# md_ver10_2.net
KiCad netlist of a schematic drawn in EAGLE
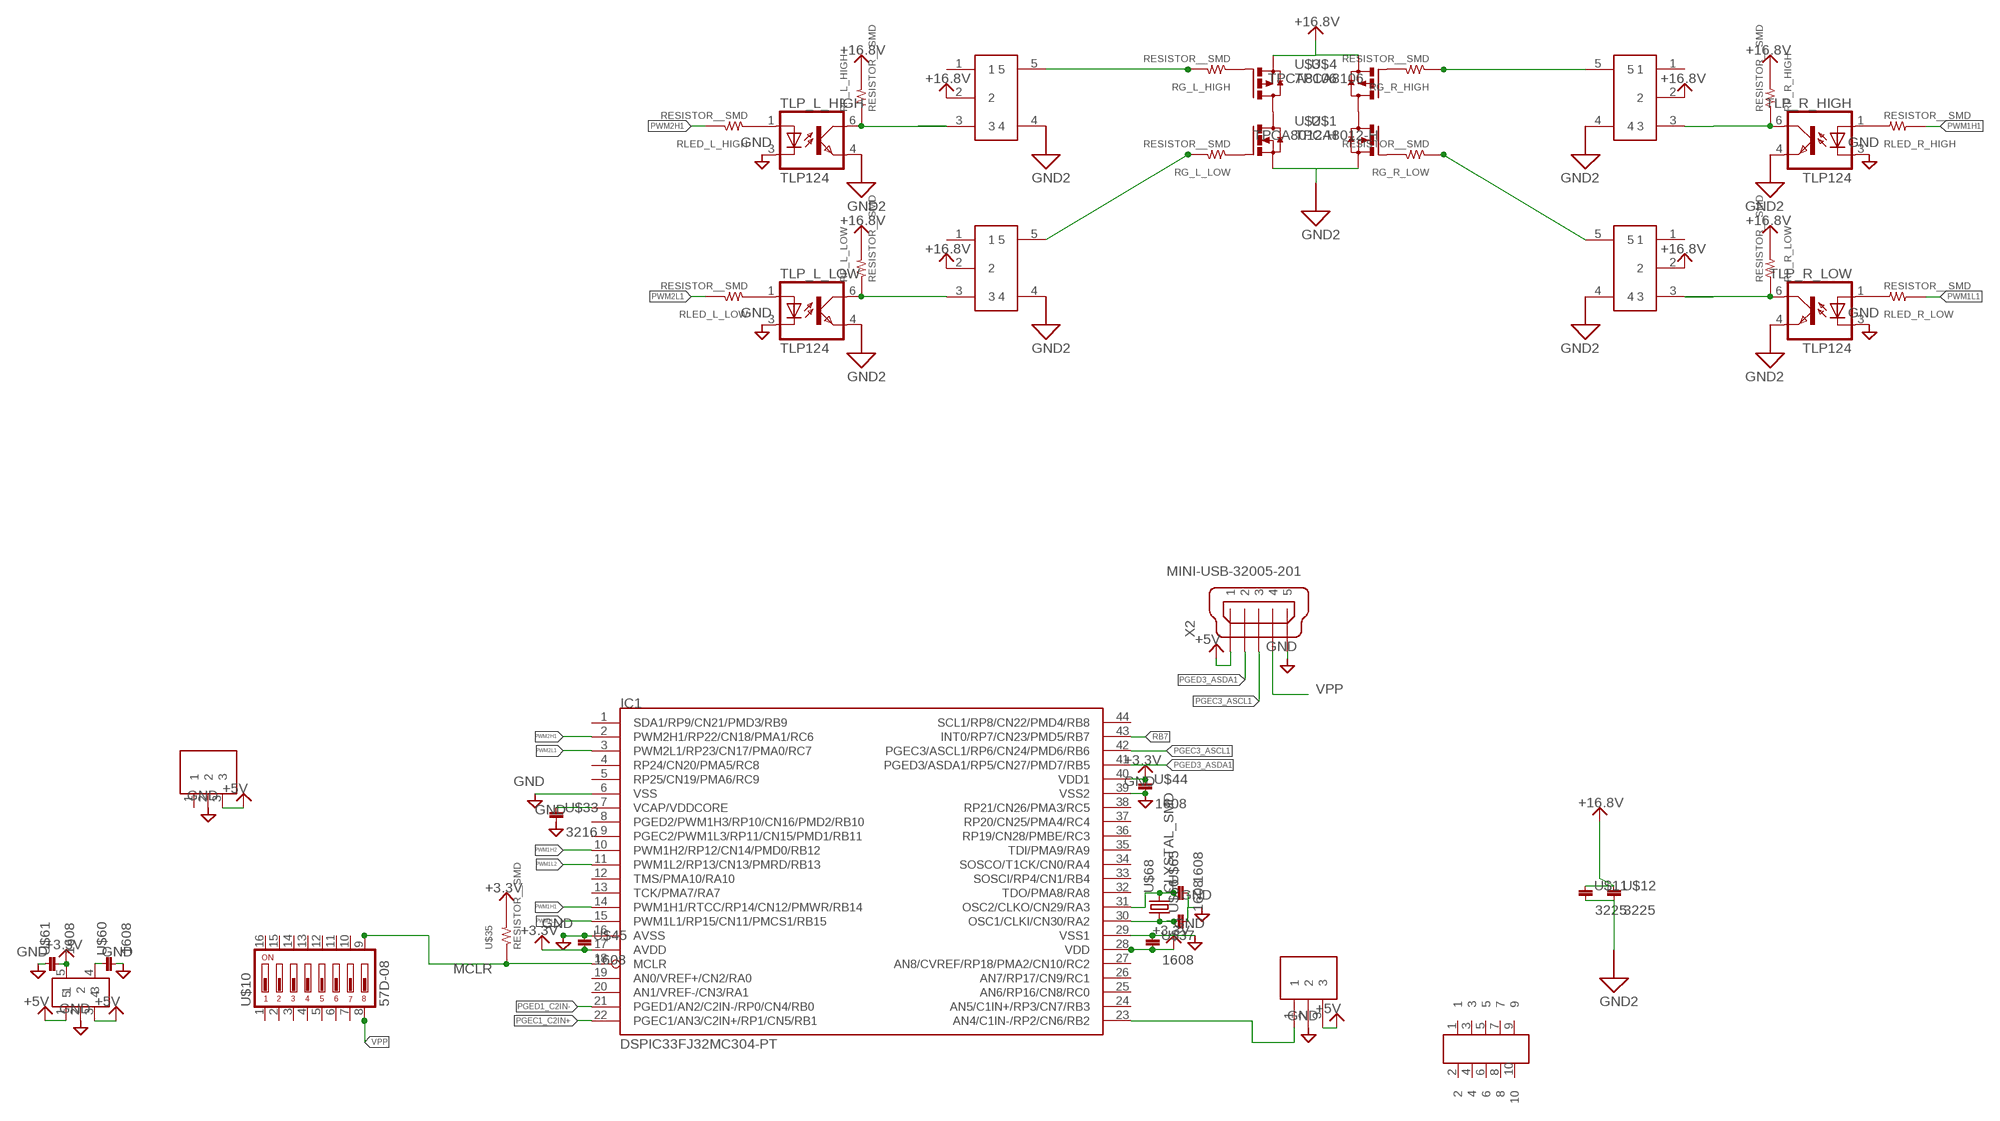
[diagram p0: schematic, sheet 1]

(export (version "E")
  (design (tool "Eeschema 10.0.6"))
  (components
    (comp (ref "IC1")
      (value "DSPIC33FJ32MC304-PT")
      (footprint "eagle-import:TQFP44")
      (libsource (lib "eagle-import") (part "DSPIC33FJ32MC304-PT"))
    )
    (comp (ref "IC_L_HIGH")
      (value "MCP1415")
      (footprint "eagle-import:SOT23-5L")
      (libsource (lib "eagle-import") (part "MCP1415"))
    )
    (comp (ref "IC_L_LOW")
      (value "MCP1415")
      (footprint "eagle-import:SOT23-5L")
      (libsource (lib "eagle-import") (part "MCP1415"))
    )
    (comp (ref "IC_R_HIGH")
      (value "MCP1415")
      (footprint "eagle-import:SOT23-5L")
      (libsource (lib "eagle-import") (part "MCP1415"))
    )
    (comp (ref "IC_R_LOW")
      (value "MCP1415")
      (footprint "eagle-import:SOT23-5L")
      (libsource (lib "eagle-import") (part "MCP1415"))
    )
    (comp (ref "RG_L_HIGH")
      (value "RESISTOR__SMD")
      (footprint "eagle-import:1608")
      (libsource (lib "eagle-import") (part "RESISTOR__SMD"))
    )
    (comp (ref "RG_L_LOW")
      (value "RESISTOR__SMD")
      (footprint "eagle-import:1608")
      (libsource (lib "eagle-import") (part "RESISTOR__SMD"))
    )
    (comp (ref "RG_R_HIGH")
      (value "RESISTOR__SMD")
      (footprint "eagle-import:1608")
      (libsource (lib "eagle-import") (part "RESISTOR__SMD"))
    )
    (comp (ref "RG_R_LOW")
      (value "RESISTOR__SMD")
      (footprint "eagle-import:1608")
      (libsource (lib "eagle-import") (part "RESISTOR__SMD"))
    )
    (comp (ref "RLED_L_HIGH")
      (value "RESISTOR__SMD")
      (footprint "eagle-import:1608")
      (libsource (lib "eagle-import") (part "RESISTOR__SMD"))
    )
    (comp (ref "RLED_L_LOW")
      (value "RESISTOR__SMD")
      (footprint "eagle-import:1608")
      (libsource (lib "eagle-import") (part "RESISTOR__SMD"))
    )
    (comp (ref "RLED_R_HIGH")
      (value "RESISTOR__SMD")
      (footprint "eagle-import:1608")
      (libsource (lib "eagle-import") (part "RESISTOR__SMD"))
    )
    (comp (ref "RLED_R_LOW")
      (value "RESISTOR__SMD")
      (footprint "eagle-import:1608")
      (libsource (lib "eagle-import") (part "RESISTOR__SMD"))
    )
    (comp (ref "RP_L_HIGH")
      (value "RESISTOR__SMD")
      (footprint "eagle-import:1608")
      (libsource (lib "eagle-import") (part "RESISTOR__SMD"))
    )
    (comp (ref "RP_L_LOW")
      (value "RESISTOR__SMD")
      (footprint "eagle-import:1608")
      (libsource (lib "eagle-import") (part "RESISTOR__SMD"))
    )
    (comp (ref "RP_R_HIGH")
      (value "RESISTOR__SMD")
      (footprint "eagle-import:1608")
      (libsource (lib "eagle-import") (part "RESISTOR__SMD"))
    )
    (comp (ref "RP_R_LOW")
      (value "RESISTOR__SMD")
      (footprint "eagle-import:1608")
      (libsource (lib "eagle-import") (part "RESISTOR__SMD"))
    )
    (comp (ref "TLP_L_HIGH")
      (value "TLP124")
      (footprint "eagle-import:11−4C1")
      (libsource (lib "eagle-import") (part "TLP124"))
    )
    (comp (ref "TLP_L_LOW")
      (value "TLP124")
      (footprint "eagle-import:11−4C1")
      (libsource (lib "eagle-import") (part "TLP124"))
    )
    (comp (ref "TLP_R_HIGH")
      (value "TLP124")
      (footprint "eagle-import:11−4C1")
      (libsource (lib "eagle-import") (part "TLP124"))
    )
    (comp (ref "TLP_R_LOW")
      (value "TLP124")
      (footprint "eagle-import:11−4C1")
      (libsource (lib "eagle-import") (part "TLP124"))
    )
    (comp (ref "U$1")
      (value "TPCA8012-H")
      (footprint "eagle-import:2-5Q1A")
      (libsource (lib "eagle-import") (part "TPCA8012-H"))
    )
    (comp (ref "U$2")
      (value "TPCA8012-H")
      (footprint "eagle-import:2-5Q1A")
      (libsource (lib "eagle-import") (part "TPCA8012-H"))
    )
    (comp (ref "U$3")
      (value "TPCA8106")
      (footprint "eagle-import:2-5Q1A")
      (libsource (lib "eagle-import") (part "TPCA8106"))
    )
    (comp (ref "U$4")
      (value "TPCA8106")
      (footprint "eagle-import:2-5Q1A")
      (libsource (lib "eagle-import") (part "TPCA8106"))
    )
    (comp (ref "U$7")
      (value "ＰＬ－ＩＲＭ")
      (footprint "eagle-import:ＰＬ－ＩＲＭ")
      (libsource (lib "eagle-import") (part "ＰＬ－ＩＲＭ"))
    )
    (comp (ref "U$8")
      (value "Ｒ－７８Ｅ５．０")
      (footprint "eagle-import:Ｒ－７８Ｅ５．０")
      (libsource (lib "eagle-import") (part "Ｒ－７８Ｅ５．０"))
    )
    (comp (ref "U$9")
      (value "TAR5SB")
      (footprint "eagle-import:SSOP5-P-0.95")
      (libsource (lib "eagle-import") (part "TAR5SB"))
    )
    (comp (ref "U$10")
      (value "57D-08")
      (footprint "eagle-import:57D")
      (libsource (lib "eagle-import") (part "57D-08"))
    )
    (comp (ref "U$11")
      (value "3225")
      (footprint "eagle-import:3225")
      (libsource (lib "eagle-import") (part "3225"))
    )
    (comp (ref "U$12")
      (value "3225")
      (footprint "eagle-import:3225")
      (libsource (lib "eagle-import") (part "3225"))
    )
    (comp (ref "U$15")
      (value "PIN_HEADER_52")
      (footprint "eagle-import:PIN_HEADER_5_2")
      (libsource (lib "eagle-import") (part "PIN_HEADER_52"))
    )
    (comp (ref "U$33")
      (value "3216")
      (footprint "eagle-import:3216")
      (libsource (lib "eagle-import") (part "3216"))
    )
    (comp (ref "U$35")
      (value "RESISTOR__SMD")
      (footprint "eagle-import:1608")
      (libsource (lib "eagle-import") (part "RESISTOR__SMD"))
    )
    (comp (ref "U$37")
      (value "1608")
      (footprint "eagle-import:1608")
      (libsource (lib "eagle-import") (part "1608"))
    )
    (comp (ref "U$44")
      (value "1608")
      (footprint "eagle-import:1608")
      (libsource (lib "eagle-import") (part "1608"))
    )
    (comp (ref "U$45")
      (value "1608")
      (footprint "eagle-import:1608")
      (libsource (lib "eagle-import") (part "1608"))
    )
    (comp (ref "U$60")
      (value "1608")
      (footprint "eagle-import:1608")
      (libsource (lib "eagle-import") (part "1608"))
    )
    (comp (ref "U$61")
      (value "1608")
      (footprint "eagle-import:1608")
      (libsource (lib "eagle-import") (part "1608"))
    )
    (comp (ref "U$65")
      (value "1608")
      (footprint "eagle-import:1608")
      (libsource (lib "eagle-import") (part "1608"))
    )
    (comp (ref "U$66")
      (value "1608")
      (footprint "eagle-import:1608")
      (libsource (lib "eagle-import") (part "1608"))
    )
    (comp (ref "U$68")
      (value "CLYSTAL_SMD")
      (footprint "eagle-import:CRYSTAL_SMD")
      (libsource (lib "eagle-import") (part "CLYSTAL_SMD"))
    )
    (comp (ref "X2")
      (value "MINI-USB-32005-201")
      (footprint "eagle-import:32005-201")
      (libsource (lib "eagle-import") (part "MINI-USB-32005-201"))
    )
  )
  (nets
    (net (code "1") (name "+3.3V") (class "Default")
      (node (ref "IC1") (pin "17") (pinfunction "AVDD_17") (pintype "power_in"))
      (node (ref "IC1") (pin "28") (pinfunction "VDD_28") (pintype "power_in"))
      (node (ref "IC1") (pin "40") (pinfunction "VDD1_40") (pintype "power_in"))
      (node (ref "U$35") (pin "2") (pinfunction "P$2_2") (pintype "passive"))
      (node (ref "U$37") (pin "P$2") (pinfunction "2_P$2") (pintype "passive"))
      (node (ref "U$44") (pin "P$1") (pinfunction "1_P$1") (pintype "passive"))
      (node (ref "U$45") (pin "P$2") (pinfunction "2_P$2") (pintype "passive"))
      (node (ref "U$61") (pin "P$2") (pinfunction "2_P$2") (pintype "passive"))
      (node (ref "U$9") (pin "5") (pinfunction "5_5") (pintype "bidirectional"))
    )
    (net (code "2") (name "+5V") (class "Default")
      (node (ref "U$7") (pin "3") (pinfunction "3_3") (pintype "bidirectional"))
      (node (ref "U$8") (pin "3") (pinfunction "3_3") (pintype "bidirectional"))
      (node (ref "U$9") (pin "1") (pinfunction "1_1") (pintype "bidirectional"))
      (node (ref "U$9") (pin "3") (pinfunction "3_3") (pintype "bidirectional"))
      (node (ref "X2") (pin "1") (pinfunction "1_1") (pintype "passive"))
    )
    (net (code "3") (name "+16.8V") (class "Default")
      (node (ref "IC_L_HIGH") (pin "2") (pinfunction "2_2") (pintype "bidirectional"))
      (node (ref "IC_L_LOW") (pin "2") (pinfunction "2_2") (pintype "bidirectional"))
      (node (ref "IC_R_HIGH") (pin "2") (pinfunction "2_2") (pintype "bidirectional"))
      (node (ref "IC_R_LOW") (pin "2") (pinfunction "2_2") (pintype "bidirectional"))
      (node (ref "RP_L_HIGH") (pin "2") (pinfunction "P$2_2") (pintype "passive"))
      (node (ref "RP_L_LOW") (pin "2") (pinfunction "P$2_2") (pintype "passive"))
      (node (ref "RP_R_HIGH") (pin "2") (pinfunction "P$2_2") (pintype "passive"))
      (node (ref "RP_R_LOW") (pin "2") (pinfunction "P$2_2") (pintype "passive"))
      (node (ref "U$11") (pin "P$1") (pinfunction "1_P$1") (pintype "passive"))
      (node (ref "U$12") (pin "P$1") (pinfunction "1_P$1") (pintype "passive"))
      (node (ref "U$3") (pin "1") (pinfunction "S_1") (pintype "passive"))
      (node (ref "U$3") (pin "2") (pinfunction "S_2") (pintype "passive"))
      (node (ref "U$3") (pin "3") (pinfunction "S_3") (pintype "passive"))
      (node (ref "U$4") (pin "1") (pinfunction "S_1") (pintype "passive"))
      (node (ref "U$4") (pin "2") (pinfunction "S_2") (pintype "passive"))
      (node (ref "U$4") (pin "3") (pinfunction "S_3") (pintype "passive"))
    )
    (net (code "4") (name "/MCLR") (class "Default")
      (node (ref "IC1") (pin "18") (pinfunction "MCLR_18") (pintype "input"))
      (node (ref "U$10") (pin "9") (pinfunction "9_9") (pintype "passive"))
      (node (ref "U$35") (pin "1") (pinfunction "P$1_1") (pintype "passive"))
    )
    (net (code "5") (name "GND") (class "Default")
      (node (ref "IC1") (pin "16") (pinfunction "AVSS_16") (pintype "power_in"))
      (node (ref "IC1") (pin "29") (pinfunction "VSS1_29") (pintype "power_in"))
      (node (ref "IC1") (pin "39") (pinfunction "VSS2_39") (pintype "power_in"))
      (node (ref "IC1") (pin "6") (pinfunction "VSS_6") (pintype "power_in"))
      (node (ref "TLP_L_HIGH") (pin "3") (pinfunction "C_3") (pintype "passive"))
      (node (ref "TLP_L_LOW") (pin "3") (pinfunction "C_3") (pintype "passive"))
      (node (ref "TLP_R_HIGH") (pin "3") (pinfunction "C_3") (pintype "passive"))
      (node (ref "TLP_R_LOW") (pin "3") (pinfunction "C_3") (pintype "passive"))
      (node (ref "U$33") (pin "P$2") (pinfunction "2_P$2") (pintype "passive"))
      (node (ref "U$37") (pin "P$1") (pinfunction "1_P$1") (pintype "passive"))
      (node (ref "U$44") (pin "P$2") (pinfunction "2_P$2") (pintype "passive"))
      (node (ref "U$45") (pin "P$1") (pinfunction "1_P$1") (pintype "passive"))
      (node (ref "U$60") (pin "P$2") (pinfunction "2_P$2") (pintype "passive"))
      (node (ref "U$61") (pin "P$1") (pinfunction "1_P$1") (pintype "passive"))
      (node (ref "U$65") (pin "P$2") (pinfunction "2_P$2") (pintype "passive"))
      (node (ref "U$66") (pin "P$2") (pinfunction "2_P$2") (pintype "passive"))
      (node (ref "U$7") (pin "2") (pinfunction "2_2") (pintype "bidirectional"))
      (node (ref "U$8") (pin "2") (pinfunction "2_2") (pintype "bidirectional"))
      (node (ref "U$9") (pin "2") (pinfunction "2_2") (pintype "bidirectional"))
      (node (ref "X2") (pin "5") (pinfunction "5_5") (pintype "passive"))
    )
    (net (code "6") (name "GND2") (class "Default")
      (node (ref "IC_L_HIGH") (pin "4") (pinfunction "4_4") (pintype "bidirectional"))
      (node (ref "IC_L_LOW") (pin "4") (pinfunction "4_4") (pintype "bidirectional"))
      (node (ref "IC_R_HIGH") (pin "4") (pinfunction "4_4") (pintype "bidirectional"))
      (node (ref "IC_R_LOW") (pin "4") (pinfunction "4_4") (pintype "bidirectional"))
      (node (ref "TLP_L_HIGH") (pin "4") (pinfunction "EMIT_4") (pintype "passive"))
      (node (ref "TLP_L_LOW") (pin "4") (pinfunction "EMIT_4") (pintype "passive"))
      (node (ref "TLP_R_HIGH") (pin "4") (pinfunction "EMIT_4") (pintype "passive"))
      (node (ref "TLP_R_LOW") (pin "4") (pinfunction "EMIT_4") (pintype "passive"))
      (node (ref "U$1") (pin "1") (pinfunction "S_1") (pintype "passive"))
      (node (ref "U$1") (pin "2") (pinfunction "S_2") (pintype "passive"))
      (node (ref "U$1") (pin "3") (pinfunction "S_3") (pintype "passive"))
      (node (ref "U$11") (pin "P$2") (pinfunction "2_P$2") (pintype "passive"))
      (node (ref "U$12") (pin "P$2") (pinfunction "2_P$2") (pintype "passive"))
      (node (ref "U$2") (pin "1") (pinfunction "S_1") (pintype "passive"))
      (node (ref "U$2") (pin "2") (pinfunction "S_2") (pintype "passive"))
      (node (ref "U$2") (pin "3") (pinfunction "S_3") (pintype "passive"))
    )
    (net (code "7") (name "Net-(IC1-AN4{slash}C1IN-{slash}RP2{slash}CN6{slash}RB2)") (class "Default")
      (node (ref "IC1") (pin "23") (pinfunction "AN4/C1IN-/RP2/CN6/RB2_23") (pintype "bidirectional"))
      (node (ref "U$7") (pin "1") (pinfunction "1_1") (pintype "bidirectional"))
    )
    (net (code "8") (name "Net-(IC1-OSC1{slash}CLKI{slash}CN30{slash}RA2)") (class "Default")
      (node (ref "IC1") (pin "30") (pinfunction "OSC1/CLKI/CN30/RA2_30") (pintype "bidirectional"))
      (node (ref "U$66") (pin "P$1") (pinfunction "1_P$1") (pintype "passive"))
      (node (ref "U$68") (pin "1") (pinfunction "1_1") (pintype "passive"))
    )
    (net (code "9") (name "Net-(IC1-OSC2{slash}CLKO{slash}CN29{slash}RA3)") (class "Default")
      (node (ref "IC1") (pin "31") (pinfunction "OSC2/CLKO/CN29/RA3_31") (pintype "bidirectional"))
      (node (ref "U$65") (pin "P$1") (pinfunction "1_P$1") (pintype "passive"))
      (node (ref "U$68") (pin "2") (pinfunction "2_2") (pintype "passive"))
    )
    (net (code "10") (name "Net-(IC1-VCAP{slash}VDDCORE)") (class "Default")
      (node (ref "IC1") (pin "7") (pinfunction "VCAP/VDDCORE_7") (pintype "power_in"))
      (node (ref "U$33") (pin "P$1") (pinfunction "1_P$1") (pintype "passive"))
    )
    (net (code "11") (name "Net-(RG_L_HIGH-P$1)") (class "Default")
      (node (ref "RG_L_HIGH") (pin "1") (pinfunction "P$1_1") (pintype "passive"))
      (node (ref "U$3") (pin "4") (pinfunction "G_4") (pintype "passive"))
    )
    (net (code "12") (name "Net-(RG_L_HIGH-P$2)") (class "Default")
      (node (ref "IC_L_HIGH") (pin "5") (pinfunction "5_5") (pintype "bidirectional"))
      (node (ref "RG_L_HIGH") (pin "2") (pinfunction "P$2_2") (pintype "passive"))
    )
    (net (code "13") (name "Net-(RG_L_LOW-P$1)") (class "Default")
      (node (ref "RG_L_LOW") (pin "1") (pinfunction "P$1_1") (pintype "passive"))
      (node (ref "U$2") (pin "4") (pinfunction "G_4") (pintype "passive"))
    )
    (net (code "14") (name "Net-(RG_L_LOW-P$2)") (class "Default")
      (node (ref "IC_L_LOW") (pin "5") (pinfunction "5_5") (pintype "bidirectional"))
      (node (ref "RG_L_LOW") (pin "2") (pinfunction "P$2_2") (pintype "passive"))
    )
    (net (code "15") (name "Net-(RG_R_HIGH-P$1)") (class "Default")
      (node (ref "IC_R_HIGH") (pin "5") (pinfunction "5_5") (pintype "bidirectional"))
      (node (ref "RG_R_HIGH") (pin "1") (pinfunction "P$1_1") (pintype "passive"))
    )
    (net (code "16") (name "Net-(RG_R_HIGH-P$2)") (class "Default")
      (node (ref "RG_R_HIGH") (pin "2") (pinfunction "P$2_2") (pintype "passive"))
      (node (ref "U$4") (pin "4") (pinfunction "G_4") (pintype "passive"))
    )
    (net (code "17") (name "Net-(RG_R_LOW-P$1)") (class "Default")
      (node (ref "IC_R_LOW") (pin "5") (pinfunction "5_5") (pintype "bidirectional"))
      (node (ref "RG_R_LOW") (pin "1") (pinfunction "P$1_1") (pintype "passive"))
    )
    (net (code "18") (name "Net-(RG_R_LOW-P$2)") (class "Default")
      (node (ref "RG_R_LOW") (pin "2") (pinfunction "P$2_2") (pintype "passive"))
      (node (ref "U$1") (pin "4") (pinfunction "G_4") (pintype "passive"))
    )
    (net (code "19") (name "Net-(RLED_L_HIGH-P$1)") (class "Default")
      (node (ref "RLED_L_HIGH") (pin "1") (pinfunction "P$1_1") (pintype "passive"))
      (node (ref "TLP_L_HIGH") (pin "1") (pinfunction "A_1") (pintype "passive"))
    )
    (net (code "20") (name "Net-(RLED_L_LOW-P$1)") (class "Default")
      (node (ref "RLED_L_LOW") (pin "1") (pinfunction "P$1_1") (pintype "passive"))
      (node (ref "TLP_L_LOW") (pin "1") (pinfunction "A_1") (pintype "passive"))
    )
    (net (code "21") (name "Net-(RLED_R_HIGH-P$1)") (class "Default")
      (node (ref "RLED_R_HIGH") (pin "1") (pinfunction "P$1_1") (pintype "passive"))
      (node (ref "TLP_R_HIGH") (pin "1") (pinfunction "A_1") (pintype "passive"))
    )
    (net (code "22") (name "Net-(RLED_R_LOW-P$1)") (class "Default")
      (node (ref "RLED_R_LOW") (pin "1") (pinfunction "P$1_1") (pintype "passive"))
      (node (ref "TLP_R_LOW") (pin "1") (pinfunction "A_1") (pintype "passive"))
    )
    (net (code "23") (name "Net-(RP_L_HIGH-P$1)") (class "Default")
      (node (ref "IC_L_HIGH") (pin "3") (pinfunction "3_3") (pintype "bidirectional"))
      (node (ref "RP_L_HIGH") (pin "1") (pinfunction "P$1_1") (pintype "passive"))
      (node (ref "TLP_L_HIGH") (pin "6") (pinfunction "COL_6") (pintype "passive"))
    )
    (net (code "24") (name "Net-(RP_L_LOW-P$1)") (class "Default")
      (node (ref "IC_L_LOW") (pin "3") (pinfunction "3_3") (pintype "bidirectional"))
      (node (ref "RP_L_LOW") (pin "1") (pinfunction "P$1_1") (pintype "passive"))
      (node (ref "TLP_L_LOW") (pin "6") (pinfunction "COL_6") (pintype "passive"))
    )
    (net (code "25") (name "Net-(RP_R_HIGH-P$1)") (class "Default")
      (node (ref "IC_R_HIGH") (pin "3") (pinfunction "3_3") (pintype "bidirectional"))
      (node (ref "RP_R_HIGH") (pin "1") (pinfunction "P$1_1") (pintype "passive"))
      (node (ref "TLP_R_HIGH") (pin "6") (pinfunction "COL_6") (pintype "passive"))
    )
    (net (code "26") (name "Net-(RP_R_LOW-P$1)") (class "Default")
      (node (ref "IC_R_LOW") (pin "3") (pinfunction "3_3") (pintype "bidirectional"))
      (node (ref "RP_R_LOW") (pin "1") (pinfunction "P$1_1") (pintype "passive"))
      (node (ref "TLP_R_LOW") (pin "6") (pinfunction "COL_6") (pintype "passive"))
    )
    (net (code "27") (name "Net-(U$1-D-Pad5)") (class "Default")
      (node (ref "U$1") (pin "5") (pinfunction "D_5") (pintype "passive"))
      (node (ref "U$1") (pin "6") (pinfunction "D_6") (pintype "passive"))
      (node (ref "U$1") (pin "7") (pinfunction "D_7") (pintype "passive"))
      (node (ref "U$1") (pin "8") (pinfunction "D_8") (pintype "passive"))
      (node (ref "U$4") (pin "5") (pinfunction "D_5") (pintype "passive"))
      (node (ref "U$4") (pin "6") (pinfunction "D_6") (pintype "passive"))
      (node (ref "U$4") (pin "7") (pinfunction "D_7") (pintype "passive"))
      (node (ref "U$4") (pin "8") (pinfunction "D_8") (pintype "passive"))
    )
    (net (code "28") (name "Net-(U$2-D-Pad5)") (class "Default")
      (node (ref "U$2") (pin "5") (pinfunction "D_5") (pintype "passive"))
      (node (ref "U$2") (pin "6") (pinfunction "D_6") (pintype "passive"))
      (node (ref "U$2") (pin "7") (pinfunction "D_7") (pintype "passive"))
      (node (ref "U$2") (pin "8") (pinfunction "D_8") (pintype "passive"))
      (node (ref "U$3") (pin "5") (pinfunction "D_5") (pintype "passive"))
      (node (ref "U$3") (pin "6") (pinfunction "D_6") (pintype "passive"))
      (node (ref "U$3") (pin "7") (pinfunction "D_7") (pintype "passive"))
      (node (ref "U$3") (pin "8") (pinfunction "D_8") (pintype "passive"))
    )
    (net (code "29") (name "Net-(U$60-1)") (class "Default")
      (node (ref "U$60") (pin "P$1") (pinfunction "1_P$1") (pintype "passive"))
      (node (ref "U$9") (pin "4") (pinfunction "4_4") (pintype "bidirectional"))
    )
    (net (code "30") (name "PGEC1_C2IN+") (class "Default")
      (node (ref "IC1") (pin "22") (pinfunction "PGEC1/AN3/C2IN+/RP1/CN5/RB1_22") (pintype "bidirectional"))
    )
    (net (code "31") (name "PGEC3_ASCL1") (class "Default")
      (node (ref "IC1") (pin "42") (pinfunction "PGEC3/ASCL1/RP6/CN24/PMD6/RB6_42") (pintype "bidirectional"))
      (node (ref "X2") (pin "3") (pinfunction "3_3") (pintype "passive"))
    )
    (net (code "32") (name "PGED1_C2IN-") (class "Default")
      (node (ref "IC1") (pin "21") (pinfunction "PGED1/AN2/C2IN-/RP0/CN4/RB0_21") (pintype "bidirectional"))
    )
    (net (code "33") (name "PGED3_ASDA1") (class "Default")
      (node (ref "IC1") (pin "41") (pinfunction "PGED3/ASDA1/RP5/CN27/PMD7/RB5_41") (pintype "bidirectional"))
      (node (ref "X2") (pin "2") (pinfunction "2_2") (pintype "passive"))
    )
    (net (code "34") (name "PWM1H1") (class "Default")
      (node (ref "IC1") (pin "14") (pinfunction "PWM1H1/RTCC/RP14/CN12/PMWR/RB14_14") (pintype "bidirectional"))
      (node (ref "RLED_R_HIGH") (pin "2") (pinfunction "P$2_2") (pintype "passive"))
    )
    (net (code "35") (name "PWM1H2") (class "Default")
      (node (ref "IC1") (pin "10") (pinfunction "PWM1H2/RP12/CN14/PMD0/RB12_10") (pintype "bidirectional"))
    )
    (net (code "36") (name "PWM1L1") (class "Default")
      (node (ref "IC1") (pin "15") (pinfunction "PWM1L1/RP15/CN11/PMCS1/RB15_15") (pintype "bidirectional"))
      (node (ref "RLED_R_LOW") (pin "2") (pinfunction "P$2_2") (pintype "passive"))
    )
    (net (code "37") (name "PWM1L2") (class "Default")
      (node (ref "IC1") (pin "11") (pinfunction "PWM1L2/RP13/CN13/PMRD/RB13_11") (pintype "bidirectional"))
    )
    (net (code "38") (name "PWM2H1") (class "Default")
      (node (ref "IC1") (pin "2") (pinfunction "PWM2H1/RP22/CN18/PMA1/RC6_2") (pintype "bidirectional"))
      (node (ref "RLED_L_HIGH") (pin "2") (pinfunction "P$2_2") (pintype "passive"))
    )
    (net (code "39") (name "PWM2L1") (class "Default")
      (node (ref "IC1") (pin "3") (pinfunction "PWM2L1/RP23/CN17/PMA0/RC7_3") (pintype "bidirectional"))
      (node (ref "RLED_L_LOW") (pin "2") (pinfunction "P$2_2") (pintype "passive"))
    )
    (net (code "40") (name "RB7") (class "Default")
      (node (ref "IC1") (pin "43") (pinfunction "INT0/RP7/CN23/PMD5/RB7_43") (pintype "bidirectional"))
    )
    (net (code "41") (name "VPP") (class "Default")
      (node (ref "U$10") (pin "8") (pinfunction "8_8") (pintype "passive"))
      (node (ref "X2") (pin "4") (pinfunction "4_4") (pintype "passive"))
    )
    (net (code "42") (name "unconnected-(IC1-AN0{slash}VREF+{slash}CN2{slash}RA0-Pad19)") (class "Default")
      (node (ref "IC1") (pin "19") (pinfunction "AN0/VREF+/CN2/RA0_19") (pintype "bidirectional"))
    )
    (net (code "43") (name "unconnected-(IC1-AN1{slash}VREF-{slash}CN3{slash}RA1-Pad20)") (class "Default")
      (node (ref "IC1") (pin "20") (pinfunction "AN1/VREF-/CN3/RA1_20") (pintype "bidirectional"))
    )
    (net (code "44") (name "unconnected-(IC1-AN5{slash}C1IN+{slash}RP3{slash}CN7{slash}RB3-Pad24)") (class "Default")
      (node (ref "IC1") (pin "24") (pinfunction "AN5/C1IN+/RP3/CN7/RB3_24") (pintype "bidirectional"))
    )
    (net (code "45") (name "unconnected-(IC1-AN6{slash}RP16{slash}CN8{slash}RC0-Pad25)") (class "Default")
      (node (ref "IC1") (pin "25") (pinfunction "AN6/RP16/CN8/RC0_25") (pintype "bidirectional"))
    )
    (net (code "46") (name "unconnected-(IC1-AN7{slash}RP17{slash}CN9{slash}RC1-Pad26)") (class "Default")
      (node (ref "IC1") (pin "26") (pinfunction "AN7/RP17/CN9/RC1_26") (pintype "bidirectional"))
    )
    (net (code "47") (name "unconnected-(IC1-AN8{slash}CVREF{slash}RP18{slash}PMA2{slash}CN10{slash}RC2-Pad27)") (class "Default")
      (node (ref "IC1") (pin "27") (pinfunction "AN8/CVREF/RP18/PMA2/CN10/RC2_27") (pintype "bidirectional"))
    )
    (net (code "48") (name "unconnected-(IC1-PGEC2{slash}PWM1L3{slash}RP11{slash}CN15{slash}PMD1{slash}RB11-Pad9)") (class "Default")
      (node (ref "IC1") (pin "9") (pinfunction "PGEC2/PWM1L3/RP11/CN15/PMD1/RB11_9") (pintype "bidirectional"))
    )
    (net (code "49") (name "unconnected-(IC1-PGED2{slash}PWM1H3{slash}RP10{slash}CN16{slash}PMD2{slash}RB10-Pad8)") (class "Default")
      (node (ref "IC1") (pin "8") (pinfunction "PGED2/PWM1H3/RP10/CN16/PMD2/RB10_8") (pintype "bidirectional"))
    )
    (net (code "50") (name "unconnected-(IC1-RP19{slash}CN28{slash}PMBE{slash}RC3-Pad36)") (class "Default")
      (node (ref "IC1") (pin "36") (pinfunction "RP19/CN28/PMBE/RC3_36") (pintype "bidirectional"))
    )
    (net (code "51") (name "unconnected-(IC1-RP20{slash}CN25{slash}PMA4{slash}RC4-Pad37)") (class "Default")
      (node (ref "IC1") (pin "37") (pinfunction "RP20/CN25/PMA4/RC4_37") (pintype "bidirectional"))
    )
    (net (code "52") (name "unconnected-(IC1-RP21{slash}CN26{slash}PMA3{slash}RC5-Pad38)") (class "Default")
      (node (ref "IC1") (pin "38") (pinfunction "RP21/CN26/PMA3/RC5_38") (pintype "bidirectional"))
    )
    (net (code "53") (name "unconnected-(IC1-RP24{slash}CN20{slash}PMA5{slash}RC8-Pad4)") (class "Default")
      (node (ref "IC1") (pin "4") (pinfunction "RP24/CN20/PMA5/RC8_4") (pintype "bidirectional"))
    )
    (net (code "54") (name "unconnected-(IC1-RP25{slash}CN19{slash}PMA6{slash}RC9-Pad5)") (class "Default")
      (node (ref "IC1") (pin "5") (pinfunction "RP25/CN19/PMA6/RC9_5") (pintype "bidirectional"))
    )
    (net (code "55") (name "unconnected-(IC1-SCL1{slash}RP8{slash}CN22{slash}PMD4{slash}RB8-Pad44)") (class "Default")
      (node (ref "IC1") (pin "44") (pinfunction "SCL1/RP8/CN22/PMD4/RB8_44") (pintype "bidirectional"))
    )
    (net (code "56") (name "unconnected-(IC1-SDA1{slash}RP9{slash}CN21{slash}PMD3{slash}RB9-Pad1)") (class "Default")
      (node (ref "IC1") (pin "1") (pinfunction "SDA1/RP9/CN21/PMD3/RB9_1") (pintype "bidirectional"))
    )
    (net (code "57") (name "unconnected-(IC1-SOSCI{slash}RP4{slash}CN1{slash}RB4-Pad33)") (class "Default")
      (node (ref "IC1") (pin "33") (pinfunction "SOSCI/RP4/CN1/RB4_33") (pintype "bidirectional"))
    )
    (net (code "58") (name "unconnected-(IC1-SOSCO{slash}T1CK{slash}CN0{slash}RA4-Pad34)") (class "Default")
      (node (ref "IC1") (pin "34") (pinfunction "SOSCO/T1CK/CN0/RA4_34") (pintype "bidirectional"))
    )
    (net (code "59") (name "unconnected-(IC1-TCK{slash}PMA7{slash}RA7-Pad13)") (class "Default")
      (node (ref "IC1") (pin "13") (pinfunction "TCK/PMA7/RA7_13") (pintype "bidirectional"))
    )
    (net (code "60") (name "unconnected-(IC1-TDI{slash}PMA9{slash}RA9-Pad35)") (class "Default")
      (node (ref "IC1") (pin "35") (pinfunction "TDI/PMA9/RA9_35") (pintype "bidirectional"))
    )
    (net (code "61") (name "unconnected-(IC1-TDO{slash}PMA8{slash}RA8-Pad32)") (class "Default")
      (node (ref "IC1") (pin "32") (pinfunction "TDO/PMA8/RA8_32") (pintype "bidirectional"))
    )
    (net (code "62") (name "unconnected-(IC1-TMS{slash}PMA10{slash}RA10-Pad12)") (class "Default")
      (node (ref "IC1") (pin "12") (pinfunction "TMS/PMA10/RA10_12") (pintype "bidirectional"))
    )
    (net (code "63") (name "unconnected-(IC_L_HIGH-Pad1)") (class "Default")
      (node (ref "IC_L_HIGH") (pin "1") (pinfunction "1_1") (pintype "bidirectional"))
    )
    (net (code "64") (name "unconnected-(IC_L_LOW-Pad1)") (class "Default")
      (node (ref "IC_L_LOW") (pin "1") (pinfunction "1_1") (pintype "bidirectional"))
    )
    (net (code "65") (name "unconnected-(IC_R_HIGH-Pad1)") (class "Default")
      (node (ref "IC_R_HIGH") (pin "1") (pinfunction "1_1") (pintype "bidirectional"))
    )
    (net (code "66") (name "unconnected-(IC_R_LOW-Pad1)") (class "Default")
      (node (ref "IC_R_LOW") (pin "1") (pinfunction "1_1") (pintype "bidirectional"))
    )
    (net (code "67") (name "unconnected-(U$8-Pad1)") (class "Default")
      (node (ref "U$8") (pin "1") (pinfunction "1_1") (pintype "bidirectional"))
    )
    (net (code "68") (name "unconnected-(U$10-Pad1)") (class "Default")
      (node (ref "U$10") (pin "1") (pinfunction "1_1") (pintype "passive"))
    )
    (net (code "69") (name "unconnected-(U$10-Pad2)") (class "Default")
      (node (ref "U$10") (pin "2") (pinfunction "2_2") (pintype "passive"))
    )
    (net (code "70") (name "unconnected-(U$10-Pad3)") (class "Default")
      (node (ref "U$10") (pin "3") (pinfunction "3_3") (pintype "passive"))
    )
    (net (code "71") (name "unconnected-(U$10-Pad4)") (class "Default")
      (node (ref "U$10") (pin "4") (pinfunction "4_4") (pintype "passive"))
    )
    (net (code "72") (name "unconnected-(U$10-Pad5)") (class "Default")
      (node (ref "U$10") (pin "5") (pinfunction "5_5") (pintype "passive"))
    )
    (net (code "73") (name "unconnected-(U$10-Pad6)") (class "Default")
      (node (ref "U$10") (pin "6") (pinfunction "6_6") (pintype "passive"))
    )
    (net (code "74") (name "unconnected-(U$10-Pad7)") (class "Default")
      (node (ref "U$10") (pin "7") (pinfunction "7_7") (pintype "passive"))
    )
    (net (code "75") (name "unconnected-(U$10-Pad10)") (class "Default")
      (node (ref "U$10") (pin "10") (pinfunction "10_10") (pintype "passive"))
    )
    (net (code "76") (name "unconnected-(U$10-Pad11)") (class "Default")
      (node (ref "U$10") (pin "11") (pinfunction "11_11") (pintype "passive"))
    )
    (net (code "77") (name "unconnected-(U$10-Pad12)") (class "Default")
      (node (ref "U$10") (pin "12") (pinfunction "12_12") (pintype "passive"))
    )
    (net (code "78") (name "unconnected-(U$10-Pad13)") (class "Default")
      (node (ref "U$10") (pin "13") (pinfunction "13_13") (pintype "passive"))
    )
    (net (code "79") (name "unconnected-(U$10-Pad14)") (class "Default")
      (node (ref "U$10") (pin "14") (pinfunction "14_14") (pintype "passive"))
    )
    (net (code "80") (name "unconnected-(U$10-Pad15)") (class "Default")
      (node (ref "U$10") (pin "15") (pinfunction "15_15") (pintype "passive"))
    )
    (net (code "81") (name "unconnected-(U$10-Pad16)") (class "Default")
      (node (ref "U$10") (pin "16") (pinfunction "16_16") (pintype "passive"))
    )
    (net (code "82") (name "unconnected-(U$15-Pad1)") (class "Default")
      (node (ref "U$15") (pin "1") (pinfunction "1_1") (pintype "bidirectional"))
    )
    (net (code "83") (name "unconnected-(U$15-Pad2)") (class "Default")
      (node (ref "U$15") (pin "2") (pinfunction "2_2") (pintype "bidirectional"))
    )
    (net (code "84") (name "unconnected-(U$15-Pad3)") (class "Default")
      (node (ref "U$15") (pin "3") (pinfunction "3_3") (pintype "bidirectional"))
    )
    (net (code "85") (name "unconnected-(U$15-Pad4)") (class "Default")
      (node (ref "U$15") (pin "4") (pinfunction "4_4") (pintype "bidirectional"))
    )
    (net (code "86") (name "unconnected-(U$15-Pad5)") (class "Default")
      (node (ref "U$15") (pin "5") (pinfunction "5_5") (pintype "bidirectional"))
    )
    (net (code "87") (name "unconnected-(U$15-Pad6)") (class "Default")
      (node (ref "U$15") (pin "6") (pinfunction "6_6") (pintype "bidirectional"))
    )
    (net (code "88") (name "unconnected-(U$15-Pad7)") (class "Default")
      (node (ref "U$15") (pin "7") (pinfunction "7_7") (pintype "bidirectional"))
    )
    (net (code "89") (name "unconnected-(U$15-Pad8)") (class "Default")
      (node (ref "U$15") (pin "8") (pinfunction "8_8") (pintype "bidirectional"))
    )
    (net (code "90") (name "unconnected-(U$15-Pad9)") (class "Default")
      (node (ref "U$15") (pin "9") (pinfunction "9_9") (pintype "bidirectional"))
    )
    (net (code "91") (name "unconnected-(U$15-Pad10)") (class "Default")
      (node (ref "U$15") (pin "10") (pinfunction "10_10") (pintype "bidirectional"))
    )
  )
)
